# miniPSU.net
KiCad netlist of a schematic drawn in EAGLE
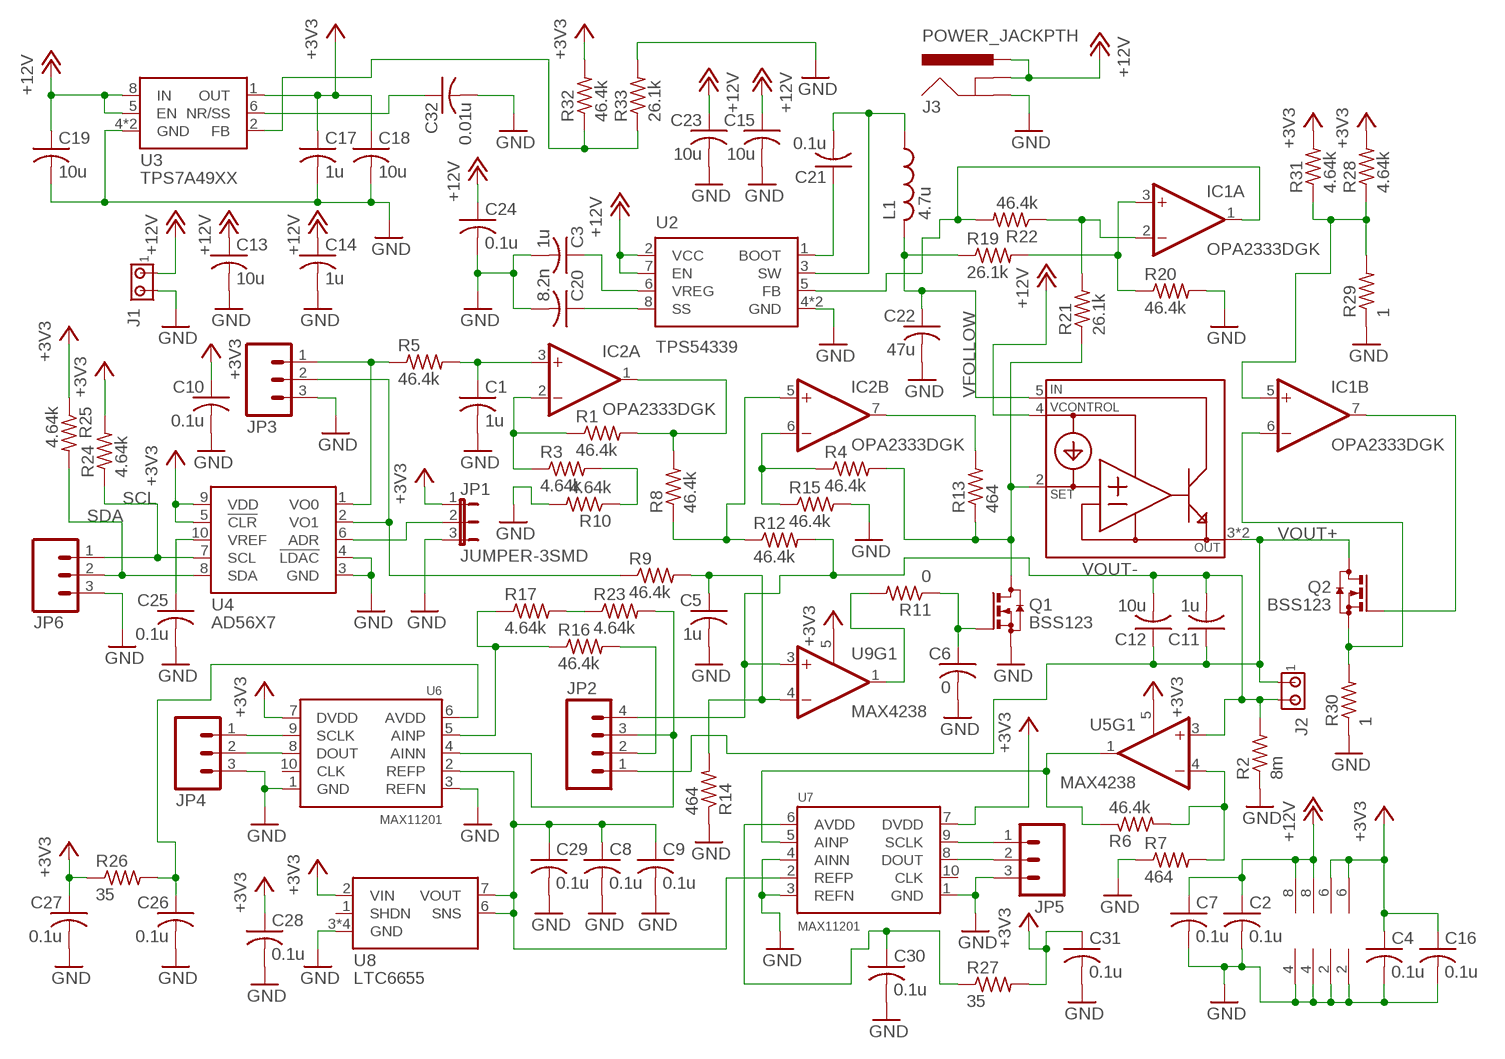
[diagram p0: schematic, sheet 1]

(export (version "E")
  (design (tool "Eeschema 10.0.6"))
  (components
    (comp (ref "C1")
      (value "1u")
      (footprint "eagle-import:C0603")
      (libsource (lib "eagle-import") (part "C-USC0603"))
    )
    (comp (ref "C2")
      (value "0.1u")
      (footprint "eagle-import:C0603")
      (libsource (lib "eagle-import") (part "C-USC0603"))
    )
    (comp (ref "C3")
      (value "1u")
      (footprint "eagle-import:C0603")
      (libsource (lib "eagle-import") (part "C-USC0603"))
    )
    (comp (ref "C4")
      (value "0.1u")
      (footprint "eagle-import:C0603")
      (libsource (lib "eagle-import") (part "C-USC0603"))
    )
    (comp (ref "C5")
      (value "1u")
      (footprint "eagle-import:C0603")
      (libsource (lib "eagle-import") (part "C-USC0603"))
    )
    (comp (ref "C6")
      (value "0")
      (footprint "eagle-import:C0603")
      (libsource (lib "eagle-import") (part "C-USC0603"))
    )
    (comp (ref "C7")
      (value "0.1u")
      (footprint "eagle-import:C0603")
      (libsource (lib "eagle-import") (part "C-USC0603"))
    )
    (comp (ref "C8")
      (value "0.1u")
      (footprint "eagle-import:C0603")
      (libsource (lib "eagle-import") (part "C-USC0603"))
    )
    (comp (ref "C9")
      (value "0.1u")
      (footprint "eagle-import:C0603")
      (libsource (lib "eagle-import") (part "C-USC0603"))
    )
    (comp (ref "C10")
      (value "0.1u")
      (footprint "eagle-import:C0603")
      (libsource (lib "eagle-import") (part "C-USC0603"))
    )
    (comp (ref "C11")
      (value "1u")
      (footprint "eagle-import:C0603")
      (libsource (lib "eagle-import") (part "C-USC0603"))
    )
    (comp (ref "C12")
      (value "10u")
      (footprint "eagle-import:C1206")
      (libsource (lib "eagle-import") (part "C-USC1206"))
    )
    (comp (ref "C13")
      (value "10u")
      (footprint "eagle-import:C1206")
      (libsource (lib "eagle-import") (part "C-USC1206"))
    )
    (comp (ref "C14")
      (value "1u")
      (footprint "eagle-import:C0603")
      (libsource (lib "eagle-import") (part "C-USC0603"))
    )
    (comp (ref "C15")
      (value "10u")
      (footprint "eagle-import:C1206")
      (libsource (lib "eagle-import") (part "C-USC1206"))
    )
    (comp (ref "C16")
      (value "0.1u")
      (footprint "eagle-import:C0603")
      (libsource (lib "eagle-import") (part "C-USC0603"))
    )
    (comp (ref "C17")
      (value "1u")
      (footprint "eagle-import:C0603")
      (libsource (lib "eagle-import") (part "C-USC0603"))
    )
    (comp (ref "C18")
      (value "10u")
      (footprint "eagle-import:C1206")
      (libsource (lib "eagle-import") (part "C-USC1206"))
    )
    (comp (ref "C19")
      (value "10u")
      (footprint "eagle-import:C1206")
      (libsource (lib "eagle-import") (part "C-USC1206"))
    )
    (comp (ref "C20")
      (value "8.2n")
      (footprint "eagle-import:C0603")
      (libsource (lib "eagle-import") (part "C-USC0603"))
    )
    (comp (ref "C21")
      (value "0.1u")
      (footprint "eagle-import:C0603")
      (libsource (lib "eagle-import") (part "C-USC0603"))
    )
    (comp (ref "C22")
      (value "47u")
      (footprint "eagle-import:C1210")
      (libsource (lib "eagle-import") (part "C-USC1210"))
    )
    (comp (ref "C23")
      (value "10u")
      (footprint "eagle-import:C1206")
      (libsource (lib "eagle-import") (part "C-USC1206"))
    )
    (comp (ref "C24")
      (value "0.1u")
      (footprint "eagle-import:C0603")
      (libsource (lib "eagle-import") (part "C-USC0603"))
    )
    (comp (ref "C25")
      (value "0.1u")
      (footprint "eagle-import:C0603")
      (libsource (lib "eagle-import") (part "C-USC0603"))
    )
    (comp (ref "C26")
      (value "0.1u")
      (footprint "eagle-import:C0603")
      (libsource (lib "eagle-import") (part "C-USC0603"))
    )
    (comp (ref "C27")
      (value "0.1u")
      (footprint "eagle-import:C0603")
      (libsource (lib "eagle-import") (part "C-USC0603"))
    )
    (comp (ref "C28")
      (value "0.1u")
      (footprint "eagle-import:C0603")
      (libsource (lib "eagle-import") (part "C-USC0603"))
    )
    (comp (ref "C29")
      (value "0.1u")
      (footprint "eagle-import:C0603")
      (libsource (lib "eagle-import") (part "C-USC0603"))
    )
    (comp (ref "C30")
      (value "0.1u")
      (footprint "eagle-import:C0603")
      (libsource (lib "eagle-import") (part "C-USC0603"))
    )
    (comp (ref "C31")
      (value "0.1u")
      (footprint "eagle-import:C0603")
      (libsource (lib "eagle-import") (part "C-USC0603"))
    )
    (comp (ref "C32")
      (value "0.01u")
      (footprint "eagle-import:C0603")
      (libsource (lib "eagle-import") (part "C-USC0603"))
    )
    (comp (ref "IC1")
      (value "OPA2333DGK")
      (footprint "eagle-import:MSOP08")
      (libsource (lib "eagle-import") (part "OPA2333DGK"))
    )
    (comp (ref "IC2")
      (value "OPA2333DGK")
      (footprint "eagle-import:MSOP08")
      (libsource (lib "eagle-import") (part "OPA2333DGK"))
    )
    (comp (ref "J1")
      (value "MTA02-156")
      (footprint "eagle-import:1X2MTA")
      (libsource (lib "eagle-import") (part "MTA02-156"))
    )
    (comp (ref "J2")
      (value "MTA02-156")
      (footprint "eagle-import:1X2MTA")
      (libsource (lib "eagle-import") (part "MTA02-156"))
    )
    (comp (ref "J3")
      (value "POWER_JACKPTH")
      (footprint "eagle-import:POWER_JACK_PTH")
      (libsource (lib "eagle-import") (part "POWER_JACKPTH"))
    )
    (comp (ref "JP1")
      (value "JUMPER-3SMD")
      (footprint "eagle-import:SJ_3")
      (libsource (lib "eagle-import") (part "JUMPER-3SMD"))
    )
    (comp (ref "JP2")
      (value "M04LOCK")
      (footprint "eagle-import:1X04_LOCK")
      (libsource (lib "eagle-import") (part "M04LOCK"))
    )
    (comp (ref "JP3")
      (value "M03LOCK")
      (footprint "eagle-import:1X03_LOCK")
      (libsource (lib "eagle-import") (part "M03LOCK"))
    )
    (comp (ref "JP4")
      (value "M03LOCK")
      (footprint "eagle-import:1X03_LOCK")
      (libsource (lib "eagle-import") (part "M03LOCK"))
    )
    (comp (ref "JP5")
      (value "M03LOCK")
      (footprint "eagle-import:1X03_LOCK")
      (libsource (lib "eagle-import") (part "M03LOCK"))
    )
    (comp (ref "JP6")
      (value "M03LOCK")
      (footprint "eagle-import:1X03_LOCK")
      (libsource (lib "eagle-import") (part "M03LOCK"))
    )
    (comp (ref "L1")
      (value "4.7u")
      (footprint "eagle-import:XAL4000")
      (libsource (lib "eagle-import") (part "L-USXAL4000"))
    )
    (comp (ref "Q1")
      (value "BSS123")
      (footprint "eagle-import:SOT23")
      (libsource (lib "eagle-import") (part "BSS123"))
    )
    (comp (ref "Q2")
      (value "BSS123")
      (footprint "eagle-import:SOT23")
      (libsource (lib "eagle-import") (part "BSS123"))
    )
    (comp (ref "R1")
      (value "46.4k")
      (footprint "eagle-import:C0603")
      (libsource (lib "eagle-import") (part "R-US0603"))
    )
    (comp (ref "R2")
      (value "8m")
      (footprint "eagle-import:C1206")
      (libsource (lib "eagle-import") (part "R-US1206"))
    )
    (comp (ref "R3")
      (value "4.64k")
      (footprint "eagle-import:C0603")
      (libsource (lib "eagle-import") (part "R-US0603"))
    )
    (comp (ref "R4")
      (value "46.4k")
      (footprint "eagle-import:C0603")
      (libsource (lib "eagle-import") (part "R-US0603"))
    )
    (comp (ref "R5")
      (value "46.4k")
      (footprint "eagle-import:C0603")
      (libsource (lib "eagle-import") (part "R-US0603"))
    )
    (comp (ref "R6")
      (value "46.4k")
      (footprint "eagle-import:C0603")
      (libsource (lib "eagle-import") (part "R-US0603"))
    )
    (comp (ref "R7")
      (value "464")
      (footprint "eagle-import:C0603")
      (libsource (lib "eagle-import") (part "R-US0603"))
    )
    (comp (ref "R8")
      (value "46.4k")
      (footprint "eagle-import:C0603")
      (libsource (lib "eagle-import") (part "R-US0603"))
    )
    (comp (ref "R9")
      (value "46.4k")
      (footprint "eagle-import:C0603")
      (libsource (lib "eagle-import") (part "R-US0603"))
    )
    (comp (ref "R10")
      (value "4.64k")
      (footprint "eagle-import:C0603")
      (libsource (lib "eagle-import") (part "R-US0603"))
    )
    (comp (ref "R11")
      (value "0")
      (footprint "eagle-import:C0603")
      (libsource (lib "eagle-import") (part "R-US0603"))
    )
    (comp (ref "R12")
      (value "46.4k")
      (footprint "eagle-import:C0603")
      (libsource (lib "eagle-import") (part "R-US0603"))
    )
    (comp (ref "R13")
      (value "464")
      (footprint "eagle-import:C0603")
      (libsource (lib "eagle-import") (part "R-US0603"))
    )
    (comp (ref "R14")
      (value "464")
      (footprint "eagle-import:C0603")
      (libsource (lib "eagle-import") (part "R-US0603"))
    )
    (comp (ref "R15")
      (value "46.4k")
      (footprint "eagle-import:C0603")
      (libsource (lib "eagle-import") (part "R-US0603"))
    )
    (comp (ref "R16")
      (value "46.4k")
      (footprint "eagle-import:C0603")
      (libsource (lib "eagle-import") (part "R-US0603"))
    )
    (comp (ref "R17")
      (value "4.64k")
      (footprint "eagle-import:C0603")
      (libsource (lib "eagle-import") (part "R-US0603"))
    )
    (comp (ref "R19")
      (value "26.1k")
      (footprint "eagle-import:C0603")
      (libsource (lib "eagle-import") (part "R-US0603"))
    )
    (comp (ref "R20")
      (value "46.4k")
      (footprint "eagle-import:C0603")
      (libsource (lib "eagle-import") (part "R-US0603"))
    )
    (comp (ref "R21")
      (value "26.1k")
      (footprint "eagle-import:C0603")
      (libsource (lib "eagle-import") (part "R-US0603"))
    )
    (comp (ref "R22")
      (value "46.4k")
      (footprint "eagle-import:C0603")
      (libsource (lib "eagle-import") (part "R-US0603"))
    )
    (comp (ref "R23")
      (value "4.64k")
      (footprint "eagle-import:C0603")
      (libsource (lib "eagle-import") (part "R-US0603"))
    )
    (comp (ref "R24")
      (value "4.64k")
      (footprint "eagle-import:C0603")
      (libsource (lib "eagle-import") (part "R-US0603"))
    )
    (comp (ref "R25")
      (value "4.64k")
      (footprint "eagle-import:C0603")
      (libsource (lib "eagle-import") (part "R-US0603"))
    )
    (comp (ref "R26")
      (value "35")
      (footprint "eagle-import:C0603")
      (libsource (lib "eagle-import") (part "R-US0603"))
    )
    (comp (ref "R27")
      (value "35")
      (footprint "eagle-import:C0603")
      (libsource (lib "eagle-import") (part "R-US0603"))
    )
    (comp (ref "R28")
      (value "4.64k")
      (footprint "eagle-import:C0603")
      (libsource (lib "eagle-import") (part "R-US0603"))
    )
    (comp (ref "R29")
      (value "1")
      (footprint "eagle-import:C0603")
      (libsource (lib "eagle-import") (part "R-US0603"))
    )
    (comp (ref "R30")
      (value "1")
      (footprint "eagle-import:C0603")
      (libsource (lib "eagle-import") (part "R-US0603"))
    )
    (comp (ref "R31")
      (value "4.64k")
      (footprint "eagle-import:C0603")
      (libsource (lib "eagle-import") (part "R-US0603"))
    )
    (comp (ref "R32")
      (value "46.4k")
      (footprint "eagle-import:C0603")
      (libsource (lib "eagle-import") (part "R-US0603"))
    )
    (comp (ref "R33")
      (value "26.1k")
      (footprint "eagle-import:C0603")
      (libsource (lib "eagle-import") (part "R-US0603"))
    )
    (comp (ref "U1")
      (value "LT3083-Q")
      (footprint "eagle-import:D2PAK-5")
      (libsource (lib "eagle-import") (part "LT3083-Q"))
    )
    (comp (ref "U2")
      (value "TPS54339")
      (footprint "eagle-import:SO-08-PAD")
      (libsource (lib "eagle-import") (part "TPS54339"))
    )
    (comp (ref "U3")
      (value "TPS7A49XX")
      (footprint "eagle-import:MSOP-8")
      (libsource (lib "eagle-import") (part "TPS7A49XX"))
    )
    (comp (ref "U4")
      (value "AD56X7")
      (footprint "eagle-import:S-PDSO-G10")
      (libsource (lib "eagle-import") (part "AD56X7"))
    )
    (comp (ref "U5")
      (value "MAX4238")
      (footprint "eagle-import:SOT23-6")
      (libsource (lib "eagle-import") (part "MAX4238"))
    )
    (comp (ref "U6")
      (value "MAX11201")
      (footprint "eagle-import:S-PDSO-G10")
      (libsource (lib "eagle-import") (part "MAX11201"))
    )
    (comp (ref "U7")
      (value "MAX11201")
      (footprint "eagle-import:S-PDSO-G10")
      (libsource (lib "eagle-import") (part "MAX11201"))
    )
    (comp (ref "U8")
      (value "LTC6655")
      (footprint "eagle-import:MSOP-8-NOPAD")
      (libsource (lib "eagle-import") (part "LTC6655"))
    )
    (comp (ref "U9")
      (value "MAX4238")
      (footprint "eagle-import:SOT23-6")
      (libsource (lib "eagle-import") (part "MAX4238"))
    )
  )
  (nets
    (net (code "1") (name "+3V3") (class "Default")
      (node (ref "C10") (pin "1") (pinfunction "1_1") (pintype "passive"))
      (node (ref "C16") (pin "1") (pinfunction "1_1") (pintype "passive"))
      (node (ref "C17") (pin "1") (pinfunction "1_1") (pintype "passive"))
      (node (ref "C18") (pin "1") (pinfunction "1_1") (pintype "passive"))
      (node (ref "C27") (pin "1") (pinfunction "1_1") (pintype "passive"))
      (node (ref "C28") (pin "1") (pinfunction "1_1") (pintype "passive"))
      (node (ref "C31") (pin "1") (pinfunction "1_1") (pintype "passive"))
      (node (ref "C4") (pin "1") (pinfunction "1_1") (pintype "passive"))
      (node (ref "JP1") (pin "1") (pinfunction "1_1") (pintype "passive"))
      (node (ref "R24") (pin "2") (pinfunction "2_2") (pintype "passive"))
      (node (ref "R25") (pin "1") (pinfunction "1_1") (pintype "passive"))
      (node (ref "R26") (pin "1") (pinfunction "1_1") (pintype "passive"))
      (node (ref "R27") (pin "2") (pinfunction "2_2") (pintype "passive"))
      (node (ref "R28") (pin "2") (pinfunction "2_2") (pintype "passive"))
      (node (ref "R31") (pin "2") (pinfunction "2_2") (pintype "passive"))
      (node (ref "R32") (pin "2") (pinfunction "2_2") (pintype "passive"))
      (node (ref "U3") (pin "1") (pinfunction "OUT_1") (pintype "power_in"))
      (node (ref "U4") (pin "5") (pinfunction "~{CLR}_5") (pintype "input"))
      (node (ref "U4") (pin "9") (pinfunction "VDD_9") (pintype "power_in"))
      (node (ref "U5") (pin "5") (pinfunction "EN_5") (pintype "input"))
      (node (ref "U5") (pin "6") (pinfunction "V+_6") (pintype "power_in"))
      (node (ref "U6") (pin "7") (pinfunction "DVDD_7") (pintype "bidirectional"))
      (node (ref "U7") (pin "7") (pinfunction "DVDD_7") (pintype "bidirectional"))
      (node (ref "U8") (pin "2") (pinfunction "VIN_2") (pintype "power_in"))
      (node (ref "U9") (pin "5") (pinfunction "EN_5") (pintype "input"))
      (node (ref "U9") (pin "6") (pinfunction "V+_6") (pintype "power_in"))
    )
    (net (code "2") (name "+12V") (class "Default")
      (node (ref "C13") (pin "1") (pinfunction "1_1") (pintype "passive"))
      (node (ref "C14") (pin "1") (pinfunction "1_1") (pintype "passive"))
      (node (ref "C15") (pin "1") (pinfunction "1_1") (pintype "passive"))
      (node (ref "C19") (pin "1") (pinfunction "1_1") (pintype "passive"))
      (node (ref "C2") (pin "1") (pinfunction "1_1") (pintype "passive"))
      (node (ref "C23") (pin "1") (pinfunction "1_1") (pintype "passive"))
      (node (ref "C24") (pin "1") (pinfunction "1_1") (pintype "passive"))
      (node (ref "C7") (pin "1") (pinfunction "1_1") (pintype "passive"))
      (node (ref "IC1") (pin "8") (pinfunction "V+_8") (pintype "power_in"))
      (node (ref "IC2") (pin "8") (pinfunction "V+_8") (pintype "power_in"))
      (node (ref "J1") (pin "1") (pinfunction "1_1") (pintype "passive"))
      (node (ref "J3") (pin "GNDBREAK") (pinfunction "GNDBREAK_GNDBREAK") (pintype "bidirectional"))
      (node (ref "J3") (pin "PWR") (pinfunction "PWR_PWR") (pintype "bidirectional"))
      (node (ref "U1") (pin "4") (pinfunction "VCONTROL_4") (pintype "power_in"))
      (node (ref "U2") (pin "2") (pinfunction "VCC_2") (pintype "power_in"))
      (node (ref "U2") (pin "7") (pinfunction "EN_7") (pintype "input"))
      (node (ref "U3") (pin "5") (pinfunction "EN_5") (pintype "input"))
      (node (ref "U3") (pin "8") (pinfunction "IN_8") (pintype "power_in"))
    )
    (net (code "3") (name "/SCL") (class "Default")
      (node (ref "JP6") (pin "1") (pinfunction "1_1") (pintype "passive"))
      (node (ref "R24") (pin "1") (pinfunction "1_1") (pintype "passive"))
      (node (ref "U4") (pin "7") (pinfunction "SCL_7") (pintype "bidirectional"))
    )
    (net (code "4") (name "/SDA") (class "Default")
      (node (ref "JP6") (pin "2") (pinfunction "2_2") (pintype "passive"))
      (node (ref "R25") (pin "2") (pinfunction "2_2") (pintype "passive"))
      (node (ref "U4") (pin "8") (pinfunction "SDA_8") (pintype "bidirectional"))
    )
    (net (code "5") (name "/VFOLLOW") (class "Default")
      (node (ref "C22") (pin "1") (pinfunction "1_1") (pintype "passive"))
      (node (ref "L1") (pin "P$2") (pinfunction "2_P$2") (pintype "passive"))
      (node (ref "R19") (pin "1") (pinfunction "1_1") (pintype "passive"))
      (node (ref "U1") (pin "5") (pinfunction "IN_5") (pintype "power_in"))
    )
    (net (code "6") (name "/VOUT+") (class "Default")
      (node (ref "C11") (pin "1") (pinfunction "1_1") (pintype "passive"))
      (node (ref "C12") (pin "1") (pinfunction "1_1") (pintype "passive"))
      (node (ref "J2") (pin "1") (pinfunction "1_1") (pintype "passive"))
      (node (ref "JP2") (pin "1") (pinfunction "1_1") (pintype "passive"))
      (node (ref "Q2") (pin "3") (pinfunction "D_3") (pintype "passive"))
      (node (ref "U1") (pin "3") (pinfunction "OUT_3") (pintype "output"))
      (node (ref "U1") (pin "PAD") (pinfunction "OUT_PAD") (pintype "output"))
    )
    (net (code "7") (name "/VOUT-") (class "Default")
      (node (ref "C11") (pin "2") (pinfunction "2_2") (pintype "passive"))
      (node (ref "C12") (pin "2") (pinfunction "2_2") (pintype "passive"))
      (node (ref "J2") (pin "2") (pinfunction "2_2") (pintype "passive"))
      (node (ref "JP2") (pin "4") (pinfunction "4_4") (pintype "passive"))
      (node (ref "R12") (pin "2") (pinfunction "2_2") (pintype "passive"))
      (node (ref "R2") (pin "2") (pinfunction "2_2") (pintype "passive"))
      (node (ref "U5") (pin "3") (pinfunction "+IN_3") (pintype "input"))
      (node (ref "U9") (pin "3") (pinfunction "+IN_3") (pintype "input"))
    )
    (net (code "8") (name "GND") (class "Default")
      (node (ref "C1") (pin "2") (pinfunction "2_2") (pintype "passive"))
      (node (ref "C10") (pin "2") (pinfunction "2_2") (pintype "passive"))
      (node (ref "C13") (pin "2") (pinfunction "2_2") (pintype "passive"))
      (node (ref "C14") (pin "2") (pinfunction "2_2") (pintype "passive"))
      (node (ref "C15") (pin "2") (pinfunction "2_2") (pintype "passive"))
      (node (ref "C16") (pin "2") (pinfunction "2_2") (pintype "passive"))
      (node (ref "C17") (pin "2") (pinfunction "2_2") (pintype "passive"))
      (node (ref "C18") (pin "2") (pinfunction "2_2") (pintype "passive"))
      (node (ref "C19") (pin "2") (pinfunction "2_2") (pintype "passive"))
      (node (ref "C2") (pin "2") (pinfunction "2_2") (pintype "passive"))
      (node (ref "C20") (pin "2") (pinfunction "2_2") (pintype "passive"))
      (node (ref "C22") (pin "2") (pinfunction "2_2") (pintype "passive"))
      (node (ref "C23") (pin "2") (pinfunction "2_2") (pintype "passive"))
      (node (ref "C24") (pin "2") (pinfunction "2_2") (pintype "passive"))
      (node (ref "C25") (pin "2") (pinfunction "2_2") (pintype "passive"))
      (node (ref "C26") (pin "2") (pinfunction "2_2") (pintype "passive"))
      (node (ref "C27") (pin "2") (pinfunction "2_2") (pintype "passive"))
      (node (ref "C28") (pin "2") (pinfunction "2_2") (pintype "passive"))
      (node (ref "C29") (pin "2") (pinfunction "2_2") (pintype "passive"))
      (node (ref "C3") (pin "2") (pinfunction "2_2") (pintype "passive"))
      (node (ref "C30") (pin "2") (pinfunction "2_2") (pintype "passive"))
      (node (ref "C31") (pin "2") (pinfunction "2_2") (pintype "passive"))
      (node (ref "C32") (pin "2") (pinfunction "2_2") (pintype "passive"))
      (node (ref "C4") (pin "2") (pinfunction "2_2") (pintype "passive"))
      (node (ref "C5") (pin "2") (pinfunction "2_2") (pintype "passive"))
      (node (ref "C6") (pin "2") (pinfunction "2_2") (pintype "passive"))
      (node (ref "C7") (pin "2") (pinfunction "2_2") (pintype "passive"))
      (node (ref "C8") (pin "2") (pinfunction "2_2") (pintype "passive"))
      (node (ref "C9") (pin "2") (pinfunction "2_2") (pintype "passive"))
      (node (ref "IC1") (pin "4") (pinfunction "V-_4") (pintype "power_in"))
      (node (ref "IC2") (pin "4") (pinfunction "V-_4") (pintype "power_in"))
      (node (ref "J1") (pin "2") (pinfunction "2_2") (pintype "passive"))
      (node (ref "J3") (pin "GND") (pinfunction "GND_GND") (pintype "bidirectional"))
      (node (ref "JP1") (pin "3") (pinfunction "3_3") (pintype "passive"))
      (node (ref "JP3") (pin "3") (pinfunction "3_3") (pintype "passive"))
      (node (ref "JP4") (pin "3") (pinfunction "3_3") (pintype "passive"))
      (node (ref "JP5") (pin "3") (pinfunction "3_3") (pintype "passive"))
      (node (ref "JP6") (pin "3") (pinfunction "3_3") (pintype "passive"))
      (node (ref "Q1") (pin "2") (pinfunction "S_2") (pintype "passive"))
      (node (ref "R10") (pin "2") (pinfunction "2_2") (pintype "passive"))
      (node (ref "R14") (pin "1") (pinfunction "1_1") (pintype "passive"))
      (node (ref "R15") (pin "2") (pinfunction "2_2") (pintype "passive"))
      (node (ref "R2") (pin "1") (pinfunction "1_1") (pintype "passive"))
      (node (ref "R20") (pin "2") (pinfunction "2_2") (pintype "passive"))
      (node (ref "R29") (pin "1") (pinfunction "1_1") (pintype "passive"))
      (node (ref "R30") (pin "1") (pinfunction "1_1") (pintype "passive"))
      (node (ref "R33") (pin "2") (pinfunction "2_2") (pintype "passive"))
      (node (ref "R7") (pin "1") (pinfunction "1_1") (pintype "passive"))
      (node (ref "U2") (pin "4") (pinfunction "GND_4") (pintype "power_in"))
      (node (ref "U2") (pin "PAD") (pinfunction "GND_PAD") (pintype "power_in"))
      (node (ref "U3") (pin "4") (pinfunction "GND_4") (pintype "power_in"))
      (node (ref "U3") (pin "TH") (pinfunction "GND_TH") (pintype "power_in"))
      (node (ref "U4") (pin "3") (pinfunction "GND_3") (pintype "power_in"))
      (node (ref "U4") (pin "4") (pinfunction "~{LDAC}_4") (pintype "input"))
      (node (ref "U5") (pin "2") (pinfunction "V-_2") (pintype "power_in"))
      (node (ref "U6") (pin "1") (pinfunction "GND_1") (pintype "bidirectional"))
      (node (ref "U6") (pin "3") (pinfunction "REFN_3") (pintype "bidirectional"))
      (node (ref "U7") (pin "1") (pinfunction "GND_1") (pintype "bidirectional"))
      (node (ref "U7") (pin "3") (pinfunction "REFN_3") (pintype "bidirectional"))
      (node (ref "U7") (pin "4") (pinfunction "AINN_4") (pintype "bidirectional"))
      (node (ref "U8") (pin "3") (pinfunction "GND_3") (pintype "power_in"))
      (node (ref "U8") (pin "4") (pinfunction "GND_4") (pintype "power_in"))
      (node (ref "U8") (pin "5") (pinfunction "GND_5") (pintype "power_in"))
      (node (ref "U8") (pin "8") (pinfunction "GND_8") (pintype "power_in"))
      (node (ref "U9") (pin "2") (pinfunction "V-_2") (pintype "power_in"))
    )
    (net (code "9") (name "Net-(IC1A-+IN)") (class "Default")
      (node (ref "IC1") (pin "3") (pinfunction "+IN_3") (pintype "input"))
      (node (ref "R19") (pin "2") (pinfunction "2_2") (pintype "passive"))
      (node (ref "R20") (pin "1") (pinfunction "1_1") (pintype "passive"))
    )
    (net (code "10") (name "Net-(IC1A--IN)") (class "Default")
      (node (ref "IC1") (pin "2") (pinfunction "-IN_2") (pintype "input"))
      (node (ref "R21") (pin "2") (pinfunction "2_2") (pintype "passive"))
      (node (ref "R22") (pin "1") (pinfunction "1_1") (pintype "passive"))
    )
    (net (code "11") (name "Net-(IC1A-OUT)") (class "Default")
      (node (ref "IC1") (pin "1") (pinfunction "OUT_1") (pintype "output"))
      (node (ref "R22") (pin "2") (pinfunction "2_2") (pintype "passive"))
      (node (ref "U2") (pin "5") (pinfunction "FB_5") (pintype "input"))
    )
    (net (code "12") (name "Net-(IC1B-+IN)") (class "Default")
      (node (ref "IC1") (pin "5") (pinfunction "+IN_5") (pintype "input"))
      (node (ref "R28") (pin "1") (pinfunction "1_1") (pintype "passive"))
      (node (ref "R29") (pin "2") (pinfunction "2_2") (pintype "passive"))
      (node (ref "R31") (pin "1") (pinfunction "1_1") (pintype "passive"))
    )
    (net (code "13") (name "Net-(IC1B--IN)") (class "Default")
      (node (ref "IC1") (pin "6") (pinfunction "-IN_6") (pintype "input"))
      (node (ref "Q2") (pin "2") (pinfunction "S_2") (pintype "passive"))
      (node (ref "R30") (pin "2") (pinfunction "2_2") (pintype "passive"))
    )
    (net (code "14") (name "Net-(IC1B-OUT)") (class "Default")
      (node (ref "IC1") (pin "7") (pinfunction "OUT_7") (pintype "output"))
      (node (ref "Q2") (pin "1") (pinfunction "G_1") (pintype "passive"))
    )
    (net (code "15") (name "Net-(IC2A-+IN)") (class "Default")
      (node (ref "C1") (pin "1") (pinfunction "1_1") (pintype "passive"))
      (node (ref "IC2") (pin "3") (pinfunction "+IN_3") (pintype "input"))
      (node (ref "R5") (pin "2") (pinfunction "2_2") (pintype "passive"))
    )
    (net (code "16") (name "Net-(IC2A--IN)") (class "Default")
      (node (ref "IC2") (pin "2") (pinfunction "-IN_2") (pintype "input"))
      (node (ref "R1") (pin "1") (pinfunction "1_1") (pintype "passive"))
      (node (ref "R3") (pin "1") (pinfunction "1_1") (pintype "passive"))
    )
    (net (code "17") (name "Net-(IC2A-OUT)") (class "Default")
      (node (ref "IC2") (pin "1") (pinfunction "OUT_1") (pintype "output"))
      (node (ref "R1") (pin "2") (pinfunction "2_2") (pintype "passive"))
      (node (ref "R8") (pin "2") (pinfunction "2_2") (pintype "passive"))
    )
    (net (code "18") (name "Net-(IC2B-+IN)") (class "Default")
      (node (ref "IC2") (pin "5") (pinfunction "+IN_5") (pintype "input"))
      (node (ref "R12") (pin "1") (pinfunction "1_1") (pintype "passive"))
      (node (ref "R8") (pin "1") (pinfunction "1_1") (pintype "passive"))
    )
    (net (code "19") (name "Net-(IC2B--IN)") (class "Default")
      (node (ref "IC2") (pin "6") (pinfunction "-IN_6") (pintype "input"))
      (node (ref "R15") (pin "1") (pinfunction "1_1") (pintype "passive"))
      (node (ref "R4") (pin "1") (pinfunction "1_1") (pintype "passive"))
    )
    (net (code "20") (name "Net-(IC2B-OUT)") (class "Default")
      (node (ref "IC2") (pin "7") (pinfunction "OUT_7") (pintype "output"))
      (node (ref "R13") (pin "2") (pinfunction "2_2") (pintype "passive"))
    )
    (net (code "21") (name "Net-(JP2-Pad2)") (class "Default")
      (node (ref "JP2") (pin "2") (pinfunction "2_2") (pintype "passive"))
      (node (ref "R16") (pin "2") (pinfunction "2_2") (pintype "passive"))
    )
    (net (code "22") (name "Net-(L1-1)") (class "Default")
      (node (ref "C21") (pin "2") (pinfunction "2_2") (pintype "passive"))
      (node (ref "L1") (pin "P$1") (pinfunction "1_P$1") (pintype "passive"))
      (node (ref "U2") (pin "3") (pinfunction "SW_3") (pintype "bidirectional"))
    )
    (net (code "23") (name "Net-(Q1-D)") (class "Default")
      (node (ref "Q1") (pin "3") (pinfunction "D_3") (pintype "passive"))
      (node (ref "R13") (pin "1") (pinfunction "1_1") (pintype "passive"))
      (node (ref "R21") (pin "1") (pinfunction "1_1") (pintype "passive"))
      (node (ref "R4") (pin "2") (pinfunction "2_2") (pintype "passive"))
      (node (ref "U1") (pin "2") (pinfunction "SET_2") (pintype "bidirectional"))
    )
    (net (code "24") (name "Net-(Q1-G)") (class "Default")
      (node (ref "C6") (pin "1") (pinfunction "1_1") (pintype "passive"))
      (node (ref "Q1") (pin "1") (pinfunction "G_1") (pintype "passive"))
      (node (ref "R11") (pin "1") (pinfunction "1_1") (pintype "passive"))
    )
    (net (code "25") (name "Net-(R10-Pad1)") (class "Default")
      (node (ref "R10") (pin "1") (pinfunction "1_1") (pintype "passive"))
      (node (ref "R3") (pin "2") (pinfunction "2_2") (pintype "passive"))
    )
    (net (code "26") (name "Net-(R17-Pad2)") (class "Default")
      (node (ref "R17") (pin "2") (pinfunction "2_2") (pintype "passive"))
      (node (ref "R23") (pin "1") (pinfunction "1_1") (pintype "passive"))
    )
    (net (code "27") (name "Net-(U2-BOOT)") (class "Default")
      (node (ref "C21") (pin "1") (pinfunction "1_1") (pintype "passive"))
      (node (ref "U2") (pin "1") (pinfunction "BOOT_1") (pintype "bidirectional"))
    )
    (net (code "28") (name "Net-(U2-SS)") (class "Default")
      (node (ref "C20") (pin "1") (pinfunction "1_1") (pintype "passive"))
      (node (ref "U2") (pin "8") (pinfunction "SS_8") (pintype "bidirectional"))
    )
    (net (code "29") (name "Net-(U2-VREG)") (class "Default")
      (node (ref "C3") (pin "1") (pinfunction "1_1") (pintype "passive"))
      (node (ref "U2") (pin "6") (pinfunction "VREG_6") (pintype "bidirectional"))
    )
    (net (code "30") (name "Net-(U3-FB)") (class "Default")
      (node (ref "R32") (pin "1") (pinfunction "1_1") (pintype "passive"))
      (node (ref "R33") (pin "1") (pinfunction "1_1") (pintype "passive"))
      (node (ref "U3") (pin "2") (pinfunction "FB_2") (pintype "bidirectional"))
    )
    (net (code "31") (name "Net-(U3-NR{slash}SS)") (class "Default")
      (node (ref "C32") (pin "1") (pinfunction "1_1") (pintype "passive"))
      (node (ref "U3") (pin "6") (pinfunction "NR/SS_6") (pintype "bidirectional"))
    )
    (net (code "32") (name "Net-(U4-ADR)") (class "Default")
      (node (ref "JP1") (pin "2") (pinfunction "2_2") (pintype "passive"))
      (node (ref "U4") (pin "6") (pinfunction "ADR_6") (pintype "input"))
    )
    (net (code "33") (name "Net-(U4-VO0)") (class "Default")
      (node (ref "JP3") (pin "1") (pinfunction "1_1") (pintype "passive"))
      (node (ref "R5") (pin "1") (pinfunction "1_1") (pintype "passive"))
      (node (ref "U4") (pin "1") (pinfunction "VO0_1") (pintype "output"))
    )
    (net (code "34") (name "Net-(U4-VO1)") (class "Default")
      (node (ref "JP3") (pin "2") (pinfunction "2_2") (pintype "passive"))
      (node (ref "R9") (pin "1") (pinfunction "1_1") (pintype "passive"))
      (node (ref "U4") (pin "2") (pinfunction "VO1_2") (pintype "output"))
    )
    (net (code "35") (name "Net-(U4-VREF)") (class "Default")
      (node (ref "C25") (pin "1") (pinfunction "1_1") (pintype "passive"))
      (node (ref "U4") (pin "10") (pinfunction "VREF_10") (pintype "power_in"))
    )
    (net (code "36") (name "Net-(U5A--IN)") (class "Default")
      (node (ref "R6") (pin "2") (pinfunction "2_2") (pintype "passive"))
      (node (ref "R7") (pin "2") (pinfunction "2_2") (pintype "passive"))
      (node (ref "U5") (pin "4") (pinfunction "-IN_4") (pintype "input"))
    )
    (net (code "37") (name "Net-(U5A-OUT)") (class "Default")
      (node (ref "R6") (pin "1") (pinfunction "1_1") (pintype "passive"))
      (node (ref "U5") (pin "1") (pinfunction "OUT_1") (pintype "output"))
      (node (ref "U7") (pin "5") (pinfunction "AINP_5") (pintype "bidirectional"))
    )
    (net (code "38") (name "Net-(U6-AINN)") (class "Default")
      (node (ref "JP2") (pin "3") (pinfunction "3_3") (pintype "passive"))
      (node (ref "R23") (pin "2") (pinfunction "2_2") (pintype "passive"))
      (node (ref "U6") (pin "4") (pinfunction "AINN_4") (pintype "bidirectional"))
    )
    (net (code "39") (name "Net-(U6-AINP)") (class "Default")
      (node (ref "R16") (pin "1") (pinfunction "1_1") (pintype "passive"))
      (node (ref "R17") (pin "1") (pinfunction "1_1") (pintype "passive"))
      (node (ref "U6") (pin "5") (pinfunction "AINP_5") (pintype "bidirectional"))
    )
    (net (code "40") (name "Net-(U6-AVDD)") (class "Default")
      (node (ref "C26") (pin "1") (pinfunction "1_1") (pintype "passive"))
      (node (ref "R26") (pin "2") (pinfunction "2_2") (pintype "passive"))
      (node (ref "U6") (pin "6") (pinfunction "AVDD_6") (pintype "bidirectional"))
    )
    (net (code "41") (name "Net-(U6-DOUT)") (class "Default")
      (node (ref "JP4") (pin "2") (pinfunction "2_2") (pintype "passive"))
      (node (ref "U6") (pin "8") (pinfunction "DOUT_8") (pintype "bidirectional"))
    )
    (net (code "42") (name "Net-(U6-REFP)") (class "Default")
      (node (ref "C29") (pin "1") (pinfunction "1_1") (pintype "passive"))
      (node (ref "C8") (pin "1") (pinfunction "1_1") (pintype "passive"))
      (node (ref "C9") (pin "1") (pinfunction "1_1") (pintype "passive"))
      (node (ref "U6") (pin "2") (pinfunction "REFP_2") (pintype "bidirectional"))
      (node (ref "U7") (pin "2") (pinfunction "REFP_2") (pintype "bidirectional"))
      (node (ref "U8") (pin "6") (pinfunction "SNS_6") (pintype "input"))
      (node (ref "U8") (pin "7") (pinfunction "VOUT_7") (pintype "output"))
    )
    (net (code "43") (name "Net-(U6-SCLK)") (class "Default")
      (node (ref "JP4") (pin "1") (pinfunction "1_1") (pintype "passive"))
      (node (ref "U6") (pin "9") (pinfunction "SCLK_9") (pintype "bidirectional"))
    )
    (net (code "44") (name "Net-(U7-AVDD)") (class "Default")
      (node (ref "C30") (pin "1") (pinfunction "1_1") (pintype "passive"))
      (node (ref "R27") (pin "1") (pinfunction "1_1") (pintype "passive"))
      (node (ref "U7") (pin "6") (pinfunction "AVDD_6") (pintype "bidirectional"))
    )
    (net (code "45") (name "Net-(U7-DOUT)") (class "Default")
      (node (ref "JP5") (pin "2") (pinfunction "2_2") (pintype "passive"))
      (node (ref "U7") (pin "8") (pinfunction "DOUT_8") (pintype "bidirectional"))
    )
    (net (code "46") (name "Net-(U7-SCLK)") (class "Default")
      (node (ref "JP5") (pin "1") (pinfunction "1_1") (pintype "passive"))
      (node (ref "U7") (pin "9") (pinfunction "SCLK_9") (pintype "bidirectional"))
    )
    (net (code "47") (name "Net-(U9A--IN)") (class "Default")
      (node (ref "C5") (pin "1") (pinfunction "1_1") (pintype "passive"))
      (node (ref "R14") (pin "2") (pinfunction "2_2") (pintype "passive"))
      (node (ref "R9") (pin "2") (pinfunction "2_2") (pintype "passive"))
      (node (ref "U9") (pin "4") (pinfunction "-IN_4") (pintype "input"))
    )
    (net (code "48") (name "Net-(U9A-OUT)") (class "Default")
      (node (ref "R11") (pin "2") (pinfunction "2_2") (pintype "passive"))
      (node (ref "U9") (pin "1") (pinfunction "OUT_1") (pintype "output"))
    )
    (net (code "49") (name "unconnected-(U6-CLK-Pad10)") (class "Default")
      (node (ref "U6") (pin "10") (pinfunction "CLK_10") (pintype "bidirectional"))
    )
    (net (code "50") (name "unconnected-(U7-CLK-Pad10)") (class "Default")
      (node (ref "U7") (pin "10") (pinfunction "CLK_10") (pintype "bidirectional"))
    )
    (net (code "51") (name "unconnected-(U8-SHDN-Pad1)") (class "Default")
      (node (ref "U8") (pin "1") (pinfunction "SHDN_1") (pintype "input"))
    )
  )
)
